# 7_-_ADC_Chip.net
KiCad netlist of a schematic drawn in Altium Designer
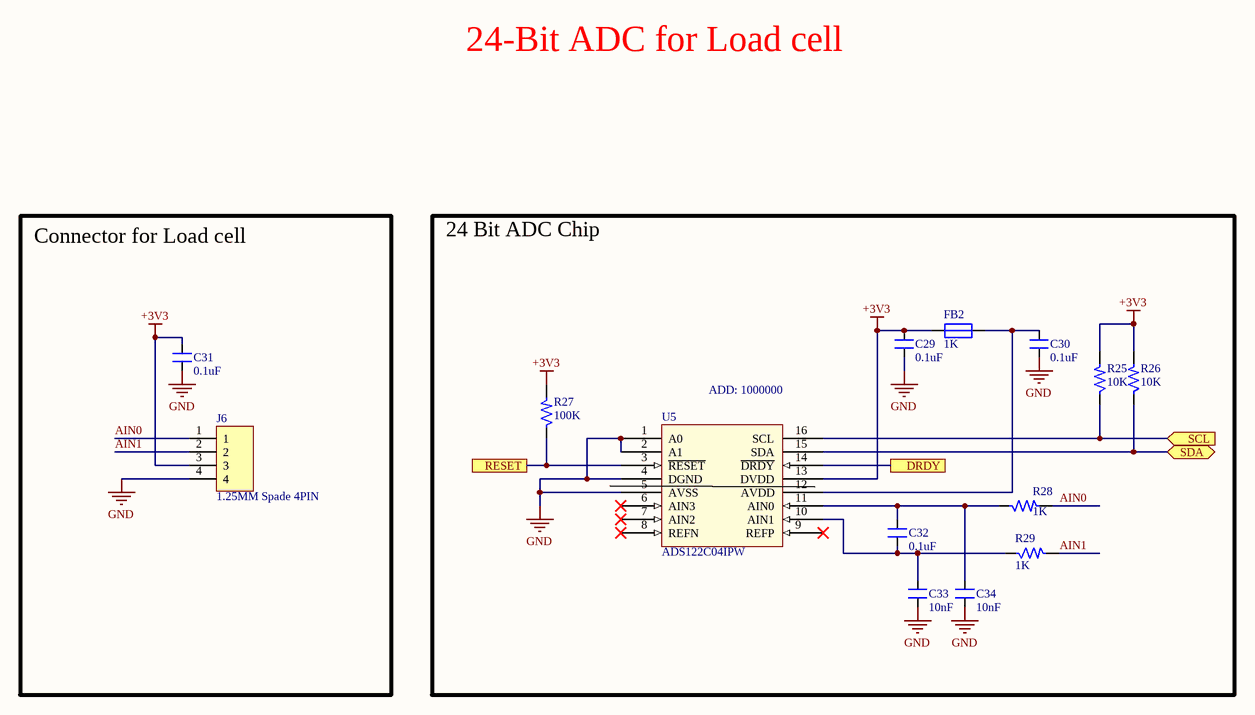
[diagram p0: [7]- ADC Chip.SchDoc]

(export (version "E")
  (design (tool "Eeschema 10.0.6"))
  (components
    (comp (ref "C29")
      (value "0.1uF")
      (footprint "CAP_0805")
      (description "0.1µF ±10% 50V Ceramic Capacitor X7R 0805 (2012 Metric)")
      (fields
        (field (name "MANUFACTURER") "Samsung")
        (field (name "MANUFACTURER PART NUMBER") "CL21B104KBCNNNC")
      )
      (libsource (lib "ESTEEMPCBLIB") (part "CAP_0.1uF-50V-10%-0805"))
    )
    (comp (ref "C30")
      (value "0.1uF")
      (footprint "CAP_0805")
      (description "0.1µF ±10% 50V Ceramic Capacitor X7R 0805 (2012 Metric)")
      (fields
        (field (name "MANUFACTURER") "Samsung")
        (field (name "MANUFACTURER PART NUMBER") "CL21B104KBCNNNC")
      )
      (libsource (lib "ESTEEMPCBLIB") (part "CAP_0.1uF-50V-10%-0805"))
    )
    (comp (ref "C31")
      (value "0.1uF")
      (footprint "CAP_0805")
      (description "0.1µF ±10% 50V Ceramic Capacitor X7R 0805 (2012 Metric)")
      (fields
        (field (name "MANUFACTURER") "Samsung")
        (field (name "MANUFACTURER PART NUMBER") "CL21B104KBCNNNC")
      )
      (libsource (lib "ESTEEMPCBLIB") (part "CAP_0.1uF-50V-10%-0805"))
    )
    (comp (ref "C32")
      (value "0.1uF")
      (footprint "CAP_0805")
      (description "0.1µF ±10% 50V Ceramic Capacitor X7R 0805 (2012 Metric)")
      (fields
        (field (name "MANUFACTURER") "Samsung")
        (field (name "MANUFACTURER PART NUMBER") "CL21B104KBCNNNC")
      )
      (libsource (lib "ESTEEMPCBLIB") (part "CAP_0.1uF-50V-10%-0805"))
    )
    (comp (ref "C33")
      (value "10nF")
      (footprint "CAP_0805")
      (description "10000pF ±10% 50V Ceramic Capacitor X7R 0805 (2012 Metric)")
      (fields
        (field (name "MANUFACTURER") "Samsung")
        (field (name "MANUFACTURER PART NUMBER") "C0805C103K5RECAUTO")
      )
      (libsource (lib "ESTEEMPCBLIB") (part "CAP_10nF-50V-10%-0805"))
    )
    (comp (ref "C34")
      (value "10nF")
      (footprint "CAP_0805")
      (description "10000pF ±10% 50V Ceramic Capacitor X7R 0805 (2012 Metric)")
      (fields
        (field (name "MANUFACTURER") "Samsung")
        (field (name "MANUFACTURER PART NUMBER") "C0805C103K5RECAUTO")
      )
      (libsource (lib "ESTEEMPCBLIB") (part "CAP_10nF-50V-10%-0805"))
    )
    (comp (ref "FB2")
      (value "1K")
      (footprint "IND_0805")
      (description "1 kOhms @ 100MHz 1 Power Line Ferrite Bead 0805 (2012 Metric) 1.6A")
      (fields
        (field (name "MANUFACTURER") "Laird")
        (field (name "MANUFACTURER PART NUMBER") "BLM21SP102SH1D")
      )
      (libsource (lib "ESTEEMPCBLIB") (part "FB_1K-100MHZ-1.6A-0805"))
    )
    (comp (ref "J6")
      (value "1.25MM Spade 4PIN")
      (footprint "CON4_50_653004117322_TH_RA")
      (description "4 Pins, 1 Row 1.25mm Pitch, right angle Connector, male")
      (fields (field (name "MANUFACTURER PART NUMBER") "653004117322") (field (name "MANUFACTURER") "JST"))
      (libsource (lib "ESTEEMPCBLIB") (part "CON-PLG_4X1-50-RA-TH"))
    )
    (comp (ref "R25")
      (value "10K")
      (footprint "RES_0603")
      (description "10 kOhms ±1% 0.1W, 1/10W Chip Resistor 0603 (1608 Metric) Automotive AEC-Q200 Thick Film")
      (fields (field (name "MANUFACTURER") "Walsin") (field (name "MANUFACTURER PART NUMBER") "WR06X1002FTL"))
      (libsource (lib "ESTEEMPCBLIB") (part "RES_10K-0.1W-1%-0603"))
    )
    (comp (ref "R26")
      (value "10K")
      (footprint "RES_0603")
      (description "10 kOhms ±1% 0.1W, 1/10W Chip Resistor 0603 (1608 Metric) Automotive AEC-Q200 Thick Film")
      (fields (field (name "MANUFACTURER") "Walsin") (field (name "MANUFACTURER PART NUMBER") "WR06X1002FTL"))
      (libsource (lib "ESTEEMPCBLIB") (part "RES_10K-0.1W-1%-0603"))
    )
    (comp (ref "R27")
      (value "100K")
      (footprint "RES_0603")
      (description "100 kOhms ±1% 0.1W, 1/10W Chip Resistor 0603 (1608 Metric) Automotive AEC-Q200 Thick Film")
      (fields
        (field (name "MANUFACTURER") "Stackpole Electronics")
        (field (name "MANUFACTURER PART NUMBER") "RMCF0603FT100K")
      )
      (libsource (lib "ESTEEMPCBLIB") (part "RES_100K-0.1W-1%-0603"))
    )
    (comp (ref "R28")
      (value "1K")
      (footprint "RES_0603")
      (description "1 kOhms ±1% 0.1W, 1/10W Chip Resistor 0603 (1608 Metric) Automotive AEC-Q200 Thick Film")
      (fields (field (name "MANUFACTURER") "Walsin") (field (name "MANUFACTURER PART NUMBER") "WR06X1001FTL"))
      (libsource (lib "ESTEEMPCBLIB") (part "RES_1K-0.1W-1%-0603"))
    )
    (comp (ref "R29")
      (value "1K")
      (footprint "RES_0603")
      (description "1 kOhms ±1% 0.1W, 1/10W Chip Resistor 0603 (1608 Metric) Automotive AEC-Q200 Thick Film")
      (fields (field (name "MANUFACTURER") "Walsin") (field (name "MANUFACTURER PART NUMBER") "WR06X1001FTL"))
      (libsource (lib "ESTEEMPCBLIB") (part "RES_1K-0.1W-1%-0603"))
    )
    (comp (ref "U5")
      (value "ADS122C04IPW")
      (footprint "TSSOP16_25-59_294_54X14_SMT")
      (description "24 Bit Analog to Digital Converter 4 Input 1 Sigma-Delta 16-TSSOP")
      (fields (field (name "MANUFACTURER") "Texas Instruments"))
      (libsource (lib "ESTEEMPCBLIB") (part "IC_ADS122C04IPW"))
    )
  )
  (nets
    (net (code "1") (name "+3V3") (class "Default")
      (node (ref "C29") (pin "2") (pinfunction "2_2") (pintype "passive"))
      (node (ref "C31") (pin "2") (pinfunction "2_2") (pintype "passive"))
      (node (ref "FB2") (pin "1") (pinfunction "1_1") (pintype "passive"))
      (node (ref "J6") (pin "3") (pinfunction "3_3") (pintype "passive"))
      (node (ref "R25") (pin "2") (pinfunction "2_2") (pintype "passive"))
      (node (ref "R26") (pin "2") (pinfunction "2_2") (pintype "passive"))
      (node (ref "R27") (pin "2") (pinfunction "2_2") (pintype "passive"))
      (node (ref "U5") (pin "13") (pinfunction "DVDD_13") (pintype "power_in"))
    )
    (net (code "2") (name "/AIN0") (class "Default")
      (node (ref "J6") (pin "1") (pinfunction "1_1") (pintype "passive"))
      (node (ref "R28") (pin "2") (pinfunction "2_2") (pintype "passive"))
    )
    (net (code "3") (name "/AIN1") (class "Default")
      (node (ref "J6") (pin "2") (pinfunction "2_2") (pintype "passive"))
      (node (ref "R29") (pin "2") (pinfunction "2_2") (pintype "passive"))
    )
    (net (code "4") (name "/DRDY") (class "Default")
      (node (ref "U5") (pin "14") (pinfunction "DRDY_14") (pintype "input"))
    )
    (net (code "5") (name "/RESET") (class "Default")
      (node (ref "R27") (pin "1") (pinfunction "1_1") (pintype "passive"))
      (node (ref "U5") (pin "3") (pinfunction "RESET_3") (pintype "input"))
    )
    (net (code "6") (name "/SCL") (class "Default")
      (node (ref "R25") (pin "1") (pinfunction "1_1") (pintype "passive"))
      (node (ref "U5") (pin "16") (pinfunction "SCL_16") (pintype "open_collector"))
    )
    (net (code "7") (name "/SDA") (class "Default")
      (node (ref "R26") (pin "1") (pinfunction "1_1") (pintype "passive"))
      (node (ref "U5") (pin "15") (pinfunction "SDA_15") (pintype "open_collector"))
    )
    (net (code "8") (name "GND") (class "Default")
      (node (ref "C29") (pin "1") (pinfunction "1_1") (pintype "passive"))
      (node (ref "C30") (pin "1") (pinfunction "1_1") (pintype "passive"))
      (node (ref "C31") (pin "1") (pinfunction "1_1") (pintype "passive"))
      (node (ref "C33") (pin "1") (pinfunction "1_1") (pintype "passive"))
      (node (ref "C34") (pin "1") (pinfunction "1_1") (pintype "passive"))
      (node (ref "J6") (pin "4") (pinfunction "4_4") (pintype "passive"))
      (node (ref "U5") (pin "1") (pinfunction "A0_1") (pintype "passive"))
      (node (ref "U5") (pin "2") (pinfunction "A1_2") (pintype "passive"))
      (node (ref "U5") (pin "4") (pinfunction "DGND_4") (pintype "power_in"))
      (node (ref "U5") (pin "5") (pinfunction "AVSS_5") (pintype "power_in"))
    )
    (net (code "9") (name "Net-(U5-AIN0)") (class "Default")
      (node (ref "C32") (pin "2") (pinfunction "2_2") (pintype "passive"))
      (node (ref "C34") (pin "2") (pinfunction "2_2") (pintype "passive"))
      (node (ref "R28") (pin "1") (pinfunction "1_1") (pintype "passive"))
      (node (ref "U5") (pin "11") (pinfunction "AIN0_11") (pintype "input"))
    )
    (net (code "10") (name "Net-(U5-AIN1)") (class "Default")
      (node (ref "C32") (pin "1") (pinfunction "1_1") (pintype "passive"))
      (node (ref "C33") (pin "2") (pinfunction "2_2") (pintype "passive"))
      (node (ref "R29") (pin "1") (pinfunction "1_1") (pintype "passive"))
      (node (ref "U5") (pin "10") (pinfunction "AIN1_10") (pintype "input"))
    )
    (net (code "11") (name "Net-(U5-AVDD)") (class "Default")
      (node (ref "C30") (pin "2") (pinfunction "2_2") (pintype "passive"))
      (node (ref "FB2") (pin "2") (pinfunction "2_2") (pintype "passive"))
      (node (ref "U5") (pin "12") (pinfunction "AVDD_12") (pintype "power_in"))
    )
    (net (code "12") (name "unconnected-(U5-AIN2-Pad7)") (class "Default")
      (node (ref "U5") (pin "7") (pinfunction "AIN2_7") (pintype "input+no_connect"))
    )
    (net (code "13") (name "unconnected-(U5-AIN3-Pad6)") (class "Default")
      (node (ref "U5") (pin "6") (pinfunction "AIN3_6") (pintype "input+no_connect"))
    )
    (net (code "14") (name "unconnected-(U5-REFN-Pad8)") (class "Default")
      (node (ref "U5") (pin "8") (pinfunction "REFN_8") (pintype "input+no_connect"))
    )
    (net (code "15") (name "unconnected-(U5-REFP-Pad9)") (class "Default")
      (node (ref "U5") (pin "9") (pinfunction "REFP_9") (pintype "input+no_connect"))
    )
  )
)
